# iron.net
KiCad netlist of a schematic drawn in EAGLE
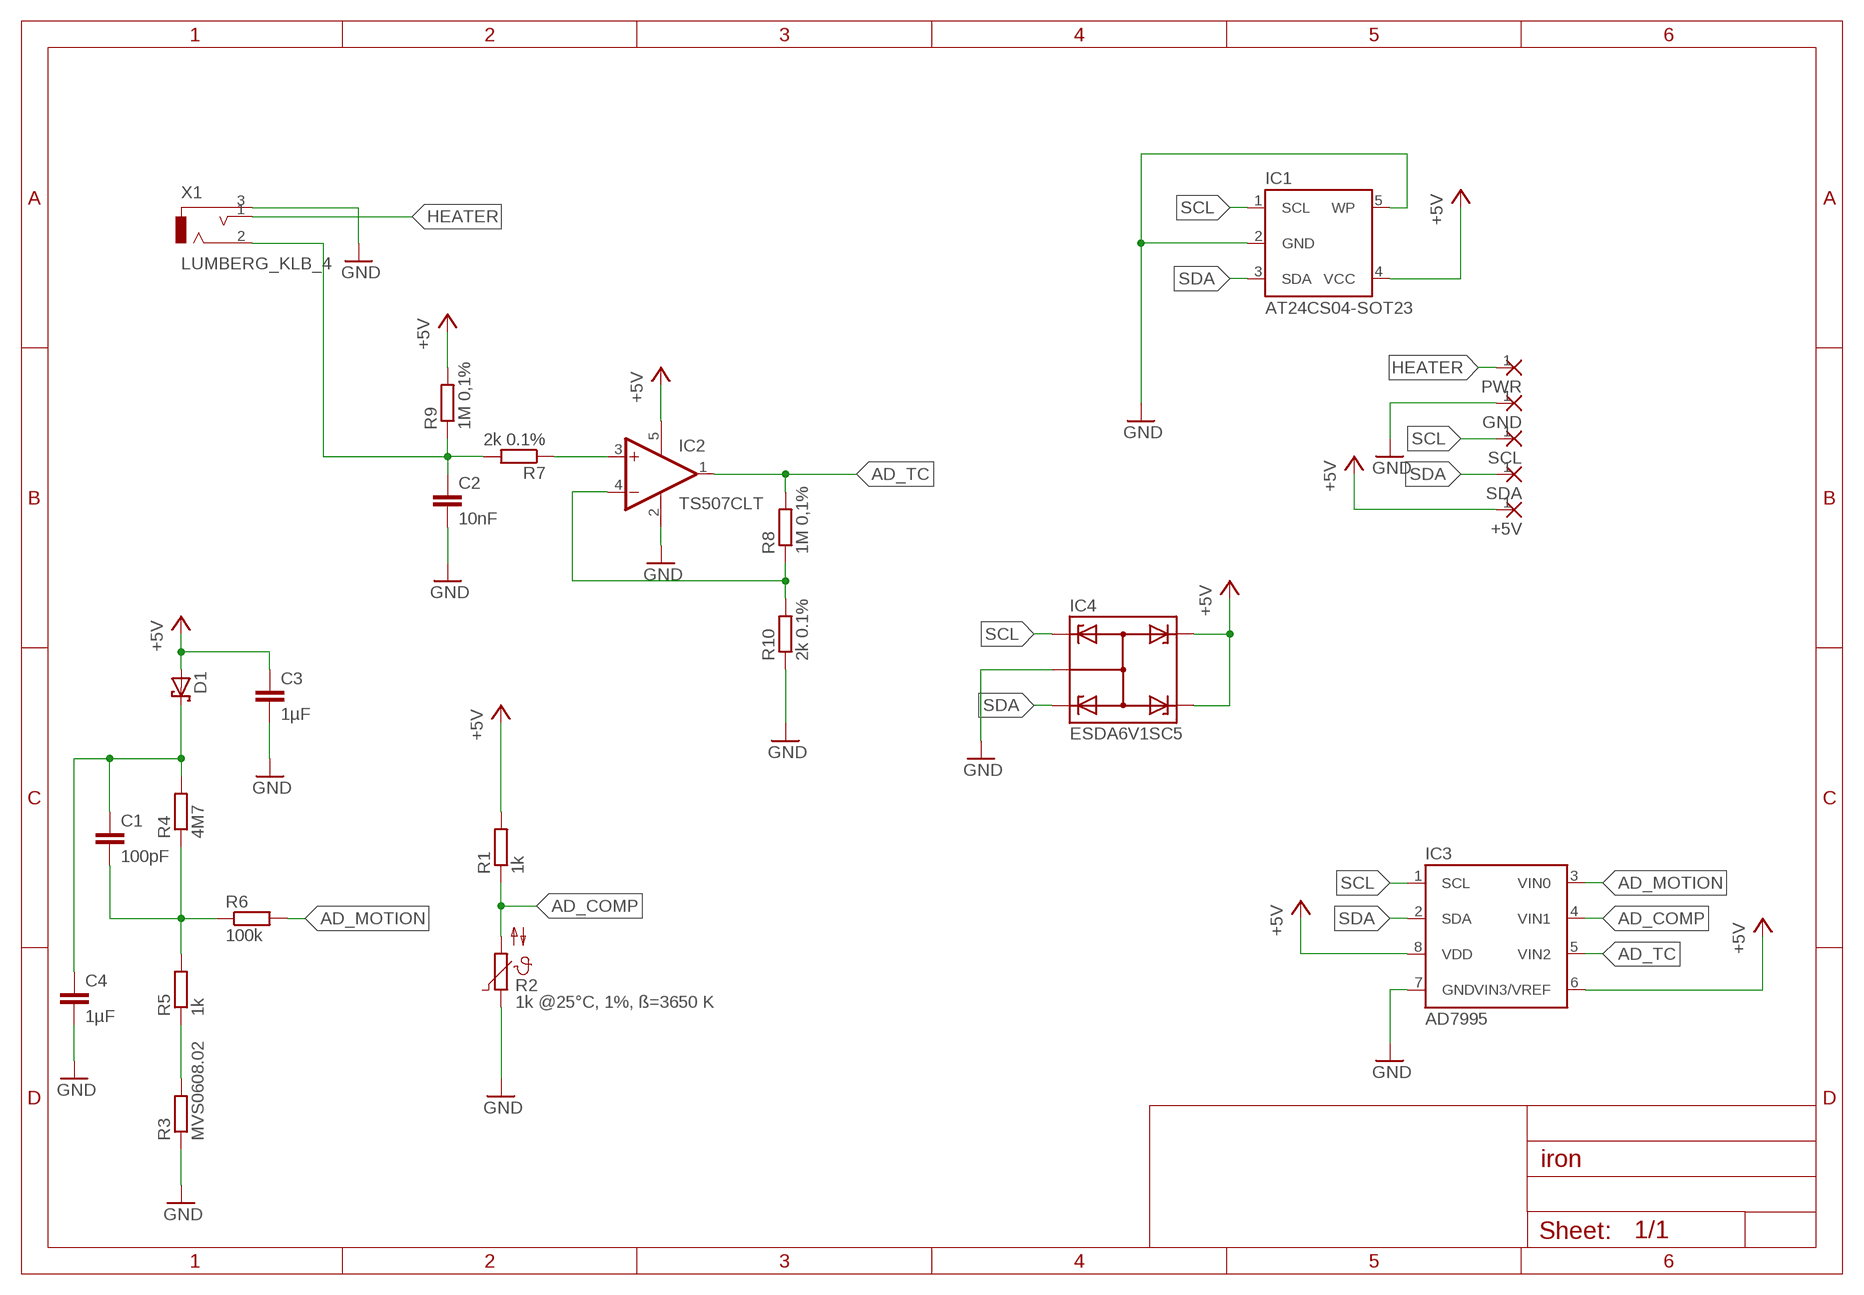
[diagram p0: schematic, sheet 1]

(export (version "E")
  (design (tool "Eeschema 10.0.6"))
  (components
    (comp (ref "+5V")
      (value "1,6/0,8")
      (footprint "eagle-import:1,6_0,8")
      (libsource (lib "eagle-import") (part "1,6/0,8"))
    )
    (comp (ref "C1")
      (value "100pF")
      (footprint "eagle-import:C0603")
      (libsource (lib "eagle-import") (part "C-EU0603"))
    )
    (comp (ref "C2")
      (value "10nF")
      (footprint "eagle-import:C0603")
      (libsource (lib "eagle-import") (part "C-EU0603"))
    )
    (comp (ref "C3")
      (value "1µF")
      (footprint "eagle-import:C0603")
      (libsource (lib "eagle-import") (part "C-EU0603"))
    )
    (comp (ref "C4")
      (value "1µF")
      (footprint "eagle-import:C0603")
      (libsource (lib "eagle-import") (part "C-EU0603"))
    )
    (comp (ref "D1")
      (value "BAT54H")
      (footprint "eagle-import:SOD123-F")
      (libsource (lib "eagle-import") (part "BAT54H"))
    )
    (comp (ref "GND")
      (value "1,6/0,8")
      (footprint "eagle-import:1,6_0,8")
      (libsource (lib "eagle-import") (part "1,6/0,8"))
    )
    (comp (ref "IC1")
      (value "AT24CS04-SOT23")
      (footprint "eagle-import:SOT23-5L")
      (libsource (lib "eagle-import") (part "AT24CS04-SOT23"))
    )
    (comp (ref "IC2")
      (value "TS507CLT")
      (footprint "eagle-import:SOT23-5L")
      (libsource (lib "eagle-import") (part "TS507CLT"))
    )
    (comp (ref "IC3")
      (value "AD7995")
      (footprint "eagle-import:SOT23-8")
      (libsource (lib "eagle-import") (part "AD7995"))
    )
    (comp (ref "IC4")
      (value "ESDA6V1SC5")
      (footprint "eagle-import:SOT23-5L")
      (libsource (lib "eagle-import") (part "ESDA6V1SC5"))
    )
    (comp (ref "PWR")
      (value "1,6/0,8")
      (footprint "eagle-import:1,6_0,8")
      (libsource (lib "eagle-import") (part "1,6/0,8"))
    )
    (comp (ref "R1")
      (value "1k")
      (footprint "eagle-import:R0603")
      (libsource (lib "eagle-import") (part "R-EU0603"))
    )
    (comp (ref "R2")
      (value "1k @25°C, 1%, ß=3650 K")
      (footprint "eagle-import:R0603")
      (libsource (lib "eagle-import") (part "NTC0603"))
    )
    (comp (ref "R3")
      (value "MVS0608.02")
      (footprint "eagle-import:VIBRA-SNS")
      (libsource (lib "eagle-import") (part "MVS0608.02"))
    )
    (comp (ref "R4")
      (value "4M7")
      (footprint "eagle-import:R0603")
      (libsource (lib "eagle-import") (part "R-EU0603"))
    )
    (comp (ref "R5")
      (value "1k")
      (footprint "eagle-import:R0603")
      (libsource (lib "eagle-import") (part "R-EU0603"))
    )
    (comp (ref "R6")
      (value "100k")
      (footprint "eagle-import:R0603")
      (libsource (lib "eagle-import") (part "R-EU0603"))
    )
    (comp (ref "R7")
      (value "2k 0.1%")
      (footprint "eagle-import:R0603")
      (libsource (lib "eagle-import") (part "R-EU0603"))
    )
    (comp (ref "R8")
      (value "1M 0,1%")
      (footprint "eagle-import:R0603")
      (libsource (lib "eagle-import") (part "R-EU0603"))
    )
    (comp (ref "R9")
      (value "1M 0,1%")
      (footprint "eagle-import:R0603")
      (libsource (lib "eagle-import") (part "R-EU0603"))
    )
    (comp (ref "R10")
      (value "2k 0.1%")
      (footprint "eagle-import:R0603")
      (libsource (lib "eagle-import") (part "R-EU0603"))
    )
    (comp (ref "SCL")
      (value "1,6/0,8")
      (footprint "eagle-import:1,6_0,8")
      (libsource (lib "eagle-import") (part "1,6/0,8"))
    )
    (comp (ref "SDA")
      (value "1,6/0,8")
      (footprint "eagle-import:1,6_0,8")
      (libsource (lib "eagle-import") (part "1,6/0,8"))
    )
    (comp (ref "X1")
      (value "LUMBERG_KLB_4")
      (footprint "eagle-import:3.5_MM_AUDIO_JACK")
      (libsource (lib "eagle-import") (part "LUMBERG_KLB_4"))
    )
  )
  (nets
    (net (code "1") (name "+5V") (class "Default")
      (node (ref "+5V") (pin "1") (pinfunction "P_1") (pintype "passive"))
      (node (ref "C3") (pin "1") (pinfunction "1_1") (pintype "passive"))
      (node (ref "D1") (pin "2") (pinfunction "A_2") (pintype "passive"))
      (node (ref "IC1") (pin "4") (pinfunction "VCC_4") (pintype "bidirectional"))
      (node (ref "IC2") (pin "5") (pinfunction "V+_5") (pintype "power_in"))
      (node (ref "IC3") (pin "6") (pinfunction "VIN3/VREF_6") (pintype "bidirectional"))
      (node (ref "IC3") (pin "8") (pinfunction "VDD_8") (pintype "bidirectional"))
      (node (ref "IC4") (pin "4") (pinfunction "4_4") (pintype "passive"))
      (node (ref "IC4") (pin "5") (pinfunction "5_5") (pintype "passive"))
      (node (ref "R1") (pin "2") (pinfunction "2_2") (pintype "passive"))
      (node (ref "R9") (pin "2") (pinfunction "2_2") (pintype "passive"))
    )
    (net (code "2") (name "AD_COMP") (class "Default")
      (node (ref "IC3") (pin "4") (pinfunction "VIN1_4") (pintype "bidirectional"))
      (node (ref "R1") (pin "1") (pinfunction "1_1") (pintype "passive"))
      (node (ref "R2") (pin "2") (pinfunction "2_2") (pintype "passive"))
    )
    (net (code "3") (name "AD_MOTION") (class "Default")
      (node (ref "IC3") (pin "3") (pinfunction "VIN0_3") (pintype "bidirectional"))
      (node (ref "R6") (pin "2") (pinfunction "2_2") (pintype "passive"))
    )
    (net (code "4") (name "AD_TC") (class "Default")
      (node (ref "IC2") (pin "1") (pinfunction "OUT_1") (pintype "output"))
      (node (ref "IC3") (pin "5") (pinfunction "VIN2_5") (pintype "bidirectional"))
      (node (ref "R8") (pin "2") (pinfunction "2_2") (pintype "passive"))
    )
    (net (code "5") (name "GND") (class "Default")
      (node (ref "C2") (pin "2") (pinfunction "2_2") (pintype "passive"))
      (node (ref "C3") (pin "2") (pinfunction "2_2") (pintype "passive"))
      (node (ref "C4") (pin "2") (pinfunction "2_2") (pintype "passive"))
      (node (ref "GND") (pin "1") (pinfunction "P_1") (pintype "passive"))
      (node (ref "IC1") (pin "2") (pinfunction "GND_2") (pintype "bidirectional"))
      (node (ref "IC1") (pin "5") (pinfunction "WP_5") (pintype "bidirectional"))
      (node (ref "IC2") (pin "2") (pinfunction "V-_2") (pintype "power_in"))
      (node (ref "IC3") (pin "7") (pinfunction "GND_7") (pintype "bidirectional"))
      (node (ref "IC4") (pin "2") (pinfunction "2_2") (pintype "passive"))
      (node (ref "R10") (pin "1") (pinfunction "1_1") (pintype "passive"))
      (node (ref "R2") (pin "1") (pinfunction "1_1") (pintype "passive"))
      (node (ref "R3") (pin "P$1") (pinfunction "1_P$1") (pintype "passive"))
      (node (ref "X1") (pin "3") (pinfunction "3_3") (pintype "passive"))
    )
    (net (code "6") (name "HEATER") (class "Default")
      (node (ref "PWR") (pin "1") (pinfunction "P_1") (pintype "passive"))
      (node (ref "X1") (pin "1") (pinfunction "1_1") (pintype "passive"))
    )
    (net (code "7") (name "Net-(C1-Pad2)") (class "Default")
      (node (ref "C1") (pin "2") (pinfunction "2_2") (pintype "passive"))
      (node (ref "R4") (pin "1") (pinfunction "1_1") (pintype "passive"))
      (node (ref "R5") (pin "2") (pinfunction "2_2") (pintype "passive"))
      (node (ref "R6") (pin "1") (pinfunction "1_1") (pintype "passive"))
    )
    (net (code "8") (name "Net-(C2-Pad1)") (class "Default")
      (node (ref "C2") (pin "1") (pinfunction "1_1") (pintype "passive"))
      (node (ref "R7") (pin "2") (pinfunction "2_2") (pintype "passive"))
      (node (ref "R9") (pin "1") (pinfunction "1_1") (pintype "passive"))
      (node (ref "X1") (pin "2") (pinfunction "2_2") (pintype "passive"))
    )
    (net (code "9") (name "Net-(D1-C)") (class "Default")
      (node (ref "C1") (pin "1") (pinfunction "1_1") (pintype "passive"))
      (node (ref "C4") (pin "1") (pinfunction "1_1") (pintype "passive"))
      (node (ref "D1") (pin "1") (pinfunction "C_1") (pintype "passive"))
      (node (ref "R4") (pin "2") (pinfunction "2_2") (pintype "passive"))
    )
    (net (code "10") (name "Net-(IC2-+IN)") (class "Default")
      (node (ref "IC2") (pin "3") (pinfunction "+IN_3") (pintype "input"))
      (node (ref "R7") (pin "1") (pinfunction "1_1") (pintype "passive"))
    )
    (net (code "11") (name "Net-(IC2--IN)") (class "Default")
      (node (ref "IC2") (pin "4") (pinfunction "-IN_4") (pintype "input"))
      (node (ref "R10") (pin "2") (pinfunction "2_2") (pintype "passive"))
      (node (ref "R8") (pin "1") (pinfunction "1_1") (pintype "passive"))
    )
    (net (code "12") (name "Net-(R3-2)") (class "Default")
      (node (ref "R3") (pin "P$2") (pinfunction "2_P$2") (pintype "passive"))
      (node (ref "R5") (pin "1") (pinfunction "1_1") (pintype "passive"))
    )
    (net (code "13") (name "SCL") (class "Default")
      (node (ref "IC1") (pin "1") (pinfunction "SCL_1") (pintype "bidirectional"))
      (node (ref "IC3") (pin "1") (pinfunction "SCL_1") (pintype "bidirectional"))
      (node (ref "IC4") (pin "1") (pinfunction "1_1") (pintype "passive"))
      (node (ref "SCL") (pin "1") (pinfunction "P_1") (pintype "passive"))
    )
    (net (code "14") (name "SDA") (class "Default")
      (node (ref "IC1") (pin "3") (pinfunction "SDA_3") (pintype "bidirectional"))
      (node (ref "IC3") (pin "2") (pinfunction "SDA_2") (pintype "bidirectional"))
      (node (ref "IC4") (pin "3") (pinfunction "3_3") (pintype "passive"))
      (node (ref "SDA") (pin "1") (pinfunction "P_1") (pintype "passive"))
    )
  )
)
